# reverb3.net
KiCad netlist of a schematic drawn in EAGLE
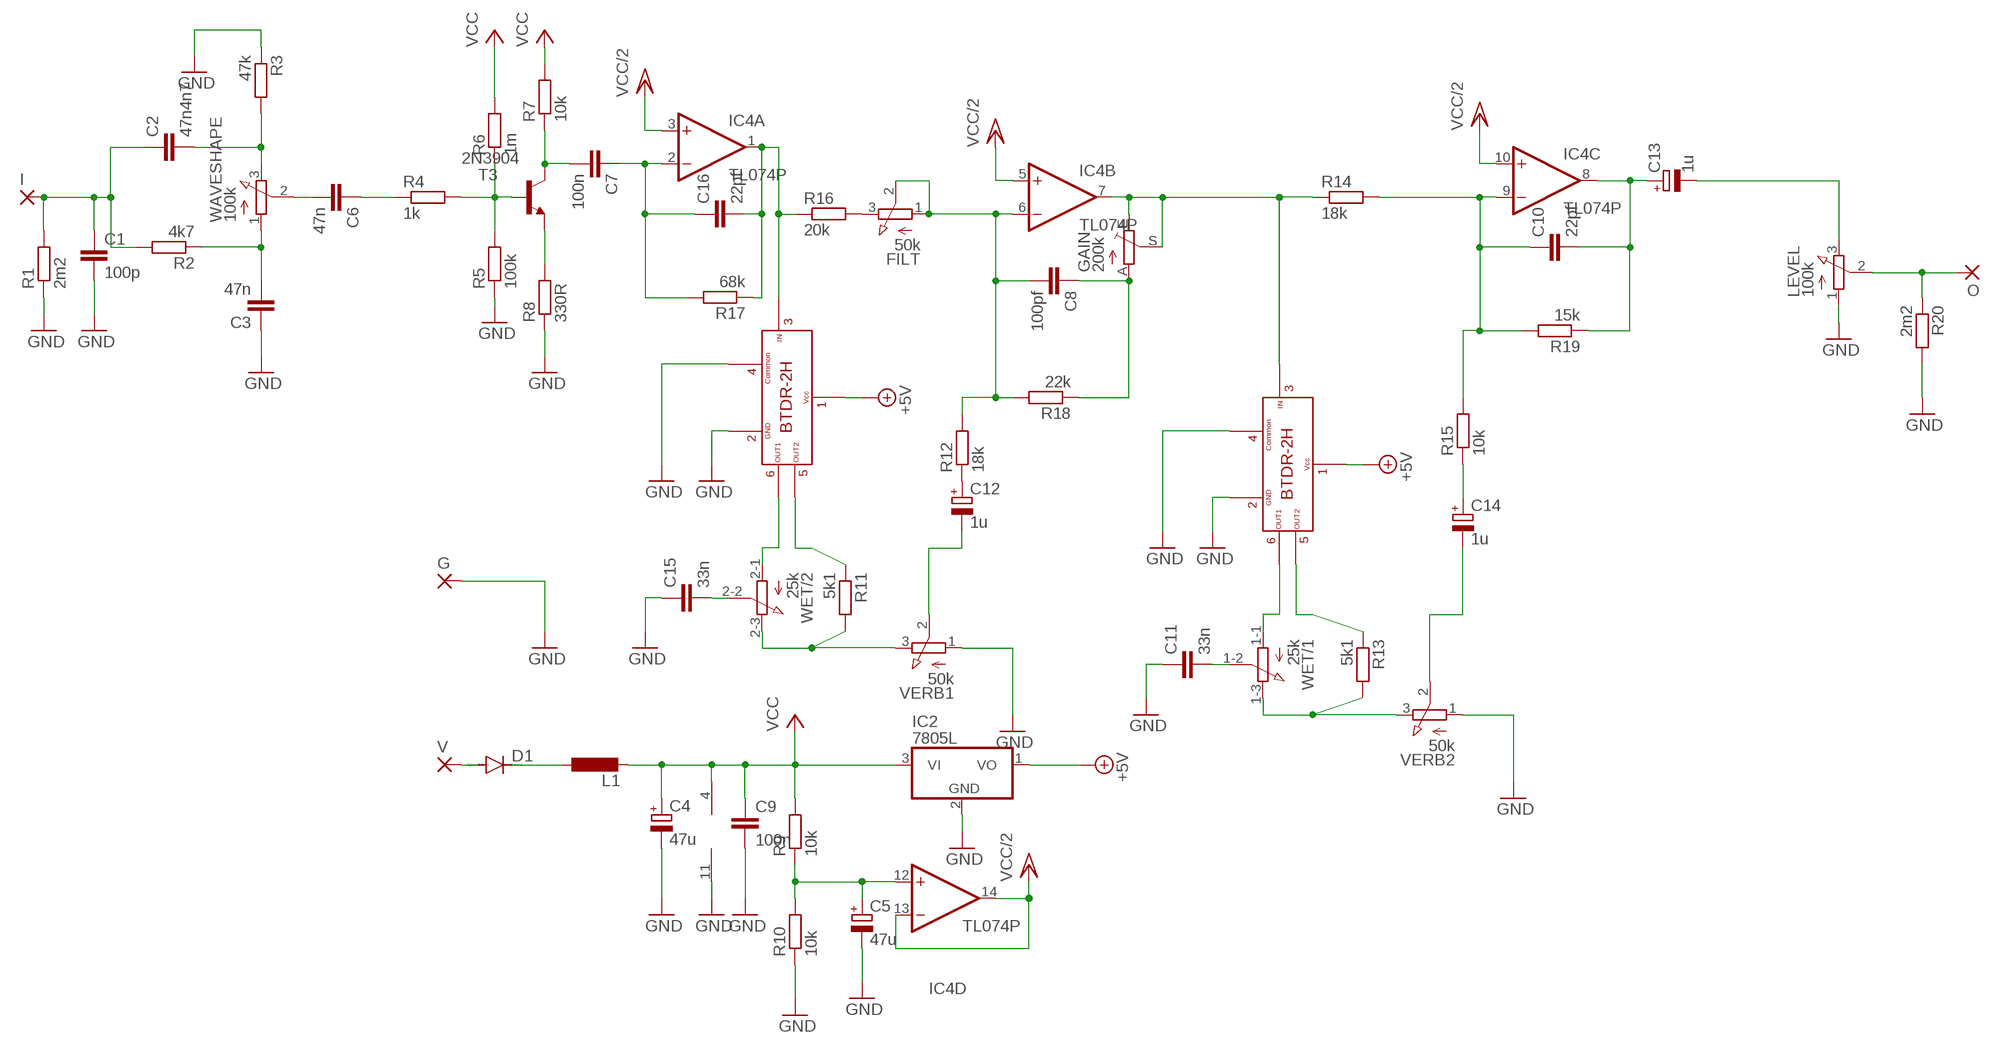
[diagram p0: schematic, sheet 1]

(export (version "E")
  (design (tool "Eeschema 10.0.6"))
  (components
    (comp (ref "BELTON1")
      (value "BTDR-2H")
      (footprint "eagle-import:BTDR2")
      (libsource (lib "eagle-import") (part "BTDR-2H"))
    )
    (comp (ref "C1")
      (value "100p")
      (footprint "eagle-import:S5MMHEXCAP")
      (libsource (lib "eagle-import") (part "C5/2.5"))
    )
    (comp (ref "C2")
      (value "47n4n7")
      (footprint "eagle-import:S5MMHEXCAP")
      (libsource (lib "eagle-import") (part "C5/2.5"))
    )
    (comp (ref "C3")
      (value "47n")
      (footprint "eagle-import:S5MMHEXCAP")
      (libsource (lib "eagle-import") (part "C5/2.5"))
    )
    (comp (ref "C4")
      (value "47u")
      (footprint "eagle-import:E2-4")
      (libsource (lib "eagle-import") (part "CPOL-EUE2-4"))
    )
    (comp (ref "C5")
      (value "47u")
      (footprint "eagle-import:E2-4")
      (libsource (lib "eagle-import") (part "CPOL-EUE2-4"))
    )
    (comp (ref "C6")
      (value "47n")
      (footprint "eagle-import:S5MMHEXCAP")
      (libsource (lib "eagle-import") (part "C5/2.5"))
    )
    (comp (ref "C7")
      (value "100n")
      (footprint "eagle-import:S5MMHEXCAP")
      (libsource (lib "eagle-import") (part "C5/2.5"))
    )
    (comp (ref "C8")
      (value "100pf")
      (footprint "eagle-import:S5MMHEXCAP")
      (libsource (lib "eagle-import") (part "C5/2.5"))
    )
    (comp (ref "C9")
      (value "100n")
      (footprint "eagle-import:S5MMHEXCAP")
      (libsource (lib "eagle-import") (part "C5/2.5"))
    )
    (comp (ref "C10")
      (value "22pf")
      (footprint "eagle-import:S5MMHEXCAP")
      (libsource (lib "eagle-import") (part "C5/2.5"))
    )
    (comp (ref "C11")
      (value "33n")
      (footprint "eagle-import:S5MMHEXCAP")
      (libsource (lib "eagle-import") (part "C5/2.5"))
    )
    (comp (ref "C12")
      (value "1u")
      (footprint "eagle-import:E2-4")
      (libsource (lib "eagle-import") (part "CPOL-EUE2-4"))
    )
    (comp (ref "C13")
      (value "1u")
      (footprint "eagle-import:E2-4")
      (libsource (lib "eagle-import") (part "CPOL-EUE2-4"))
    )
    (comp (ref "C14")
      (value "1u")
      (footprint "eagle-import:E2-4")
      (libsource (lib "eagle-import") (part "CPOL-EUE2-4"))
    )
    (comp (ref "C15")
      (value "33n")
      (footprint "eagle-import:S5MMHEXCAP")
      (libsource (lib "eagle-import") (part "C5/2.5"))
    )
    (comp (ref "C16")
      (value "22pf")
      (footprint "eagle-import:S5MMHEXCAP")
      (libsource (lib "eagle-import") (part "C5/2.5"))
    )
    (comp (ref "D1")
      (value "1N4148DO35-7")
      (footprint "eagle-import:DO35-7")
      (libsource (lib "eagle-import") (part "1N4148DO35-7"))
    )
    (comp (ref "FILT")
      (value "50k")
      (footprint "eagle-import:3RP_1610N")
      (libsource (lib "eagle-import") (part "HEXPOT1"))
    )
    (comp (ref "G")
      (value "WIREPAD1,6/0,9")
      (footprint "eagle-import:1,6_0,9")
      (libsource (lib "eagle-import") (part "WIREPAD1,6/0,9"))
    )
    (comp (ref "GAIN")
      (value "200k")
      (footprint "eagle-import:CT6")
      (libsource (lib "eagle-import") (part "TRIM_EU-CT6"))
    )
    (comp (ref "I")
      (value "WIREPAD1,6/0,9")
      (footprint "eagle-import:1,6_0,9")
      (libsource (lib "eagle-import") (part "WIREPAD1,6/0,9"))
    )
    (comp (ref "IC2")
      (value "7805L")
      (footprint "eagle-import:TO92")
      (libsource (lib "eagle-import") (part "78L05"))
    )
    (comp (ref "IC4")
      (value "TL074P")
      (footprint "eagle-import:DIL14")
      (libsource (lib "eagle-import") (part "TL074P"))
    )
    (comp (ref "L1")
      (value "L-EU0204/7")
      (footprint "eagle-import:0204_7")
      (libsource (lib "eagle-import") (part "L-EU0204/7"))
    )
    (comp (ref "LEVEL")
      (value "100k")
      (footprint "eagle-import:3RP_1610N")
      (libsource (lib "eagle-import") (part "HEXPOT1"))
    )
    (comp (ref "O")
      (value "WIREPAD1,6/0,9")
      (footprint "eagle-import:1,6_0,9")
      (libsource (lib "eagle-import") (part "WIREPAD1,6/0,9"))
    )
    (comp (ref "R1")
      (value "2m2")
      (footprint "eagle-import:0207_7")
      (libsource (lib "eagle-import") (part "R-EU_0207/7"))
    )
    (comp (ref "R2")
      (value "4k7")
      (footprint "eagle-import:0207_7")
      (libsource (lib "eagle-import") (part "R-EU_0207/7"))
    )
    (comp (ref "R3")
      (value "47k")
      (footprint "eagle-import:0207_7")
      (libsource (lib "eagle-import") (part "R-EU_0207/7"))
    )
    (comp (ref "R4")
      (value "1k")
      (footprint "eagle-import:0207_7")
      (libsource (lib "eagle-import") (part "R-EU_0207/7"))
    )
    (comp (ref "R5")
      (value "100k")
      (footprint "eagle-import:0207_7")
      (libsource (lib "eagle-import") (part "R-EU_0207/7"))
    )
    (comp (ref "R6")
      (value "1m")
      (footprint "eagle-import:0207_7")
      (libsource (lib "eagle-import") (part "R-EU_0207/7"))
    )
    (comp (ref "R7")
      (value "10k")
      (footprint "eagle-import:0207_7")
      (libsource (lib "eagle-import") (part "R-EU_0207/7"))
    )
    (comp (ref "R8")
      (value "330R")
      (footprint "eagle-import:0207_7")
      (libsource (lib "eagle-import") (part "R-EU_0207/7"))
    )
    (comp (ref "R9")
      (value "10k")
      (footprint "eagle-import:0207_7")
      (libsource (lib "eagle-import") (part "R-EU_0207/7"))
    )
    (comp (ref "R10")
      (value "10k")
      (footprint "eagle-import:0207_7")
      (libsource (lib "eagle-import") (part "R-EU_0207/7"))
    )
    (comp (ref "R11")
      (value "5k1")
      (footprint "eagle-import:0207_7")
      (libsource (lib "eagle-import") (part "R-EU_0207/7"))
    )
    (comp (ref "R12")
      (value "18k")
      (footprint "eagle-import:0207_7")
      (libsource (lib "eagle-import") (part "R-EU_0207/7"))
    )
    (comp (ref "R13")
      (value "5k1")
      (footprint "eagle-import:0207_7")
      (libsource (lib "eagle-import") (part "R-EU_0207/7"))
    )
    (comp (ref "R14")
      (value "18k")
      (footprint "eagle-import:0207_7")
      (libsource (lib "eagle-import") (part "R-EU_0207/7"))
    )
    (comp (ref "R15")
      (value "10k")
      (footprint "eagle-import:0207_7")
      (libsource (lib "eagle-import") (part "R-EU_0207/7"))
    )
    (comp (ref "R16")
      (value "20k")
      (footprint "eagle-import:0207_7")
      (libsource (lib "eagle-import") (part "R-EU_0207/7"))
    )
    (comp (ref "R17")
      (value "68k")
      (footprint "eagle-import:0207_7")
      (libsource (lib "eagle-import") (part "R-EU_0207/7"))
    )
    (comp (ref "R18")
      (value "22k")
      (footprint "eagle-import:0207_7")
      (libsource (lib "eagle-import") (part "R-EU_0207/7"))
    )
    (comp (ref "R19")
      (value "15k")
      (footprint "eagle-import:0207_7")
      (libsource (lib "eagle-import") (part "R-EU_0207/7"))
    )
    (comp (ref "R20")
      (value "2m2")
      (footprint "eagle-import:0207_7")
      (libsource (lib "eagle-import") (part "R-EU_0207/7"))
    )
    (comp (ref "T3")
      (value "2N3904")
      (footprint "eagle-import:TO92")
      (libsource (lib "eagle-import") (part "2N3904"))
    )
    (comp (ref "U$2")
      (value "BTDR-2H")
      (footprint "eagle-import:BTDR2")
      (libsource (lib "eagle-import") (part "BTDR-2H"))
    )
    (comp (ref "V")
      (value "WIREPAD1,6/0,9")
      (footprint "eagle-import:1,6_0,9")
      (libsource (lib "eagle-import") (part "WIREPAD1,6/0,9"))
    )
    (comp (ref "VERB1")
      (value "50k")
      (footprint "eagle-import:3RP_1610N")
      (libsource (lib "eagle-import") (part "HEXPOT1"))
    )
    (comp (ref "VERB2")
      (value "50k")
      (footprint "eagle-import:3RP_1610N")
      (libsource (lib "eagle-import") (part "HEXPOT1"))
    )
    (comp (ref "WAVESHAPE")
      (value "100k")
      (footprint "eagle-import:3RP_1610N")
      (libsource (lib "eagle-import") (part "HEXPOT1"))
    )
    (comp (ref "WET")
      (value "25k")
      (footprint "eagle-import:3RP_1610G")
      (libsource (lib "eagle-import") (part "3RP/1610G"))
    )
  )
  (nets
    (net (code "1") (name "+5V") (class "Default")
      (node (ref "BELTON1") (pin "P$1") (pinfunction "P$1_P$1") (pintype "bidirectional"))
      (node (ref "IC2") (pin "1") (pinfunction "VO_1") (pintype "passive"))
      (node (ref "U$2") (pin "P$1") (pinfunction "P$1_P$1") (pintype "bidirectional"))
    )
    (net (code "2") (name "GND") (class "Default")
      (node (ref "BELTON1") (pin "P$2") (pinfunction "P$2_P$2") (pintype "bidirectional"))
      (node (ref "BELTON1") (pin "P$4") (pinfunction "P$4_P$4") (pintype "bidirectional"))
      (node (ref "C1") (pin "2") (pinfunction "2_2") (pintype "passive"))
      (node (ref "C11") (pin "1") (pinfunction "1_1") (pintype "passive"))
      (node (ref "C15") (pin "1") (pinfunction "1_1") (pintype "passive"))
      (node (ref "C3") (pin "1") (pinfunction "1_1") (pintype "passive"))
      (node (ref "C4") (pin "-") (pinfunction "-_-") (pintype "passive"))
      (node (ref "C5") (pin "-") (pinfunction "-_-") (pintype "passive"))
      (node (ref "C9") (pin "2") (pinfunction "2_2") (pintype "passive"))
      (node (ref "G") (pin "1") (pinfunction "P_1") (pintype "passive"))
      (node (ref "IC2") (pin "2") (pinfunction "GND_2") (pintype "passive"))
      (node (ref "IC4") (pin "11") (pinfunction "V-_11") (pintype "power_in"))
      (node (ref "LEVEL") (pin "1") (pinfunction "A_1") (pintype "passive"))
      (node (ref "R1") (pin "1") (pinfunction "1_1") (pintype "passive"))
      (node (ref "R10") (pin "1") (pinfunction "1_1") (pintype "passive"))
      (node (ref "R20") (pin "2") (pinfunction "2_2") (pintype "passive"))
      (node (ref "R3") (pin "1") (pinfunction "1_1") (pintype "passive"))
      (node (ref "R5") (pin "1") (pinfunction "1_1") (pintype "passive"))
      (node (ref "R8") (pin "1") (pinfunction "1_1") (pintype "passive"))
      (node (ref "U$2") (pin "P$2") (pinfunction "P$2_P$2") (pintype "bidirectional"))
      (node (ref "U$2") (pin "P$4") (pinfunction "P$4_P$4") (pintype "bidirectional"))
      (node (ref "VERB1") (pin "1") (pinfunction "A_1") (pintype "passive"))
      (node (ref "VERB2") (pin "1") (pinfunction "A_1") (pintype "passive"))
    )
    (net (code "3") (name "Net-(BELTON1-PadP$5)") (class "Default")
      (node (ref "BELTON1") (pin "P$5") (pinfunction "P$5_P$5") (pintype "bidirectional"))
      (node (ref "R13") (pin "1") (pinfunction "1_1") (pintype "passive"))
    )
    (net (code "4") (name "Net-(C6-Pad1)") (class "Default")
      (node (ref "C6") (pin "1") (pinfunction "1_1") (pintype "passive"))
      (node (ref "R4") (pin "1") (pinfunction "1_1") (pintype "passive"))
    )
    (net (code "5") (name "Net-(C8-Pad1)") (class "Default")
      (node (ref "C8") (pin "1") (pinfunction "1_1") (pintype "passive"))
      (node (ref "GAIN") (pin "A") (pinfunction "A_A") (pintype "passive"))
      (node (ref "R18") (pin "1") (pinfunction "1_1") (pintype "passive"))
    )
    (net (code "6") (name "Net-(C12-Pad+)") (class "Default")
      (node (ref "C12") (pin "+") (pinfunction "+_+") (pintype "passive"))
      (node (ref "R12") (pin "1") (pinfunction "1_1") (pintype "passive"))
    )
    (net (code "7") (name "Net-(C14-Pad+)") (class "Default")
      (node (ref "C14") (pin "+") (pinfunction "+_+") (pintype "passive"))
      (node (ref "R15") (pin "1") (pinfunction "1_1") (pintype "passive"))
    )
    (net (code "8") (name "Net-(D1-PadC)") (class "Default")
      (node (ref "D1") (pin "C") (pinfunction "C_C") (pintype "passive"))
      (node (ref "L1") (pin "1") (pinfunction "1_1") (pintype "passive"))
    )
    (net (code "9") (name "Net-(FILT-A)") (class "Default")
      (node (ref "C8") (pin "2") (pinfunction "2_2") (pintype "passive"))
      (node (ref "FILT") (pin "1") (pinfunction "A_1") (pintype "passive"))
      (node (ref "FILT") (pin "2") (pinfunction "S_2") (pintype "passive"))
      (node (ref "IC4") (pin "6") (pinfunction "-IN_6") (pintype "input"))
      (node (ref "R12") (pin "2") (pinfunction "2_2") (pintype "passive"))
      (node (ref "R18") (pin "2") (pinfunction "2_2") (pintype "passive"))
    )
    (net (code "10") (name "Net-(FILT-E)") (class "Default")
      (node (ref "FILT") (pin "3") (pinfunction "E_3") (pintype "passive"))
      (node (ref "R16") (pin "2") (pinfunction "2_2") (pintype "passive"))
    )
    (net (code "11") (name "Net-(I-P)") (class "Default")
      (node (ref "C1") (pin "1") (pinfunction "1_1") (pintype "passive"))
      (node (ref "C2") (pin "1") (pinfunction "1_1") (pintype "passive"))
      (node (ref "I") (pin "1") (pinfunction "P_1") (pintype "passive"))
      (node (ref "R1") (pin "2") (pinfunction "2_2") (pintype "passive"))
      (node (ref "R2") (pin "2") (pinfunction "2_2") (pintype "passive"))
    )
    (net (code "12") (name "Net-(IC4A--IN)") (class "Default")
      (node (ref "C16") (pin "1") (pinfunction "1_1") (pintype "passive"))
      (node (ref "C7") (pin "1") (pinfunction "1_1") (pintype "passive"))
      (node (ref "IC4") (pin "2") (pinfunction "-IN_2") (pintype "input"))
      (node (ref "R17") (pin "2") (pinfunction "2_2") (pintype "passive"))
    )
    (net (code "13") (name "Net-(IC4A-OUT)") (class "Default")
      (node (ref "C16") (pin "2") (pinfunction "2_2") (pintype "passive"))
      (node (ref "IC4") (pin "1") (pinfunction "OUT_1") (pintype "output"))
      (node (ref "R16") (pin "1") (pinfunction "1_1") (pintype "passive"))
      (node (ref "R17") (pin "1") (pinfunction "1_1") (pintype "passive"))
      (node (ref "U$2") (pin "P$3") (pinfunction "P$3_P$3") (pintype "bidirectional"))
    )
    (net (code "14") (name "Net-(IC4B-OUT)") (class "Default")
      (node (ref "BELTON1") (pin "P$3") (pinfunction "P$3_P$3") (pintype "bidirectional"))
      (node (ref "GAIN") (pin "E") (pinfunction "E_E") (pintype "passive"))
      (node (ref "GAIN") (pin "S") (pinfunction "S_S") (pintype "passive"))
      (node (ref "IC4") (pin "7") (pinfunction "OUT_7") (pintype "output"))
      (node (ref "R14") (pin "1") (pinfunction "1_1") (pintype "passive"))
    )
    (net (code "15") (name "Net-(IC4C--IN)") (class "Default")
      (node (ref "C10") (pin "1") (pinfunction "1_1") (pintype "passive"))
      (node (ref "IC4") (pin "9") (pinfunction "-IN_9") (pintype "input"))
      (node (ref "R14") (pin "2") (pinfunction "2_2") (pintype "passive"))
      (node (ref "R15") (pin "2") (pinfunction "2_2") (pintype "passive"))
      (node (ref "R19") (pin "2") (pinfunction "2_2") (pintype "passive"))
    )
    (net (code "16") (name "Net-(IC4C-OUT)") (class "Default")
      (node (ref "C10") (pin "2") (pinfunction "2_2") (pintype "passive"))
      (node (ref "C13") (pin "+") (pinfunction "+_+") (pintype "passive"))
      (node (ref "IC4") (pin "8") (pinfunction "OUT_8") (pintype "output"))
      (node (ref "R19") (pin "1") (pinfunction "1_1") (pintype "passive"))
    )
    (net (code "17") (name "Net-(IC4D-+IN)") (class "Default")
      (node (ref "C5") (pin "+") (pinfunction "+_+") (pintype "passive"))
      (node (ref "IC4") (pin "12") (pinfunction "+IN_12") (pintype "input"))
      (node (ref "R10") (pin "2") (pinfunction "2_2") (pintype "passive"))
      (node (ref "R9") (pin "1") (pinfunction "1_1") (pintype "passive"))
    )
    (net (code "18") (name "Net-(LEVEL-E)") (class "Default")
      (node (ref "C13") (pin "-") (pinfunction "-_-") (pintype "passive"))
      (node (ref "LEVEL") (pin "3") (pinfunction "E_3") (pintype "passive"))
    )
    (net (code "19") (name "Net-(LEVEL-S)") (class "Default")
      (node (ref "LEVEL") (pin "2") (pinfunction "S_2") (pintype "passive"))
      (node (ref "O") (pin "1") (pinfunction "P_1") (pintype "passive"))
      (node (ref "R20") (pin "1") (pinfunction "1_1") (pintype "passive"))
    )
    (net (code "20") (name "Net-(R11-Pad1)") (class "Default")
      (node (ref "R11") (pin "1") (pinfunction "1_1") (pintype "passive"))
      (node (ref "U$2") (pin "P$5") (pinfunction "P$5_P$5") (pintype "bidirectional"))
    )
    (net (code "21") (name "Net-(T3-B)") (class "Default")
      (node (ref "R4") (pin "2") (pinfunction "2_2") (pintype "passive"))
      (node (ref "R5") (pin "2") (pinfunction "2_2") (pintype "passive"))
      (node (ref "R6") (pin "1") (pinfunction "1_1") (pintype "passive"))
      (node (ref "T3") (pin "2") (pinfunction "B_2") (pintype "passive"))
    )
    (net (code "22") (name "Net-(T3-C)") (class "Default")
      (node (ref "C7") (pin "2") (pinfunction "2_2") (pintype "passive"))
      (node (ref "R7") (pin "1") (pinfunction "1_1") (pintype "passive"))
      (node (ref "T3") (pin "1") (pinfunction "C_1") (pintype "passive"))
    )
    (net (code "23") (name "Net-(T3-E)") (class "Default")
      (node (ref "R8") (pin "2") (pinfunction "2_2") (pintype "passive"))
      (node (ref "T3") (pin "3") (pinfunction "E_3") (pintype "passive"))
    )
    (net (code "24") (name "Net-(V-P)") (class "Default")
      (node (ref "D1") (pin "A") (pinfunction "A_A") (pintype "passive"))
      (node (ref "V") (pin "1") (pinfunction "P_1") (pintype "passive"))
    )
    (net (code "25") (name "Net-(VERB1-E)") (class "Default")
      (node (ref "R11") (pin "2") (pinfunction "2_2") (pintype "passive"))
      (node (ref "VERB1") (pin "3") (pinfunction "E_3") (pintype "passive"))
      (node (ref "WET") (pin "2-3") (pinfunction "E_2-3") (pintype "passive"))
    )
    (net (code "26") (name "Net-(VERB1-S)") (class "Default")
      (node (ref "C12") (pin "-") (pinfunction "-_-") (pintype "passive"))
      (node (ref "VERB1") (pin "2") (pinfunction "S_2") (pintype "passive"))
    )
    (net (code "27") (name "Net-(VERB2-E)") (class "Default")
      (node (ref "R13") (pin "2") (pinfunction "2_2") (pintype "passive"))
      (node (ref "VERB2") (pin "3") (pinfunction "E_3") (pintype "passive"))
      (node (ref "WET") (pin "1-3") (pinfunction "E_1-3") (pintype "passive"))
    )
    (net (code "28") (name "Net-(VERB2-S)") (class "Default")
      (node (ref "C14") (pin "-") (pinfunction "-_-") (pintype "passive"))
      (node (ref "VERB2") (pin "2") (pinfunction "S_2") (pintype "passive"))
    )
    (net (code "29") (name "Net-(WAVESHAPE-A)") (class "Default")
      (node (ref "C3") (pin "2") (pinfunction "2_2") (pintype "passive"))
      (node (ref "R2") (pin "1") (pinfunction "1_1") (pintype "passive"))
      (node (ref "WAVESHAPE") (pin "1") (pinfunction "A_1") (pintype "passive"))
    )
    (net (code "30") (name "Net-(WAVESHAPE-E)") (class "Default")
      (node (ref "C2") (pin "2") (pinfunction "2_2") (pintype "passive"))
      (node (ref "R3") (pin "2") (pinfunction "2_2") (pintype "passive"))
      (node (ref "WAVESHAPE") (pin "3") (pinfunction "E_3") (pintype "passive"))
    )
    (net (code "31") (name "Net-(WAVESHAPE-S)") (class "Default")
      (node (ref "C6") (pin "2") (pinfunction "2_2") (pintype "passive"))
      (node (ref "WAVESHAPE") (pin "2") (pinfunction "S_2") (pintype "passive"))
    )
    (net (code "32") (name "Net-(WETA-A)") (class "Default")
      (node (ref "BELTON1") (pin "P$6") (pinfunction "P$6_P$6") (pintype "bidirectional"))
      (node (ref "WET") (pin "1-1") (pinfunction "A_1-1") (pintype "passive"))
    )
    (net (code "33") (name "Net-(WETA-S)") (class "Default")
      (node (ref "C11") (pin "2") (pinfunction "2_2") (pintype "passive"))
      (node (ref "WET") (pin "1-2") (pinfunction "S_1-2") (pintype "passive"))
    )
    (net (code "34") (name "Net-(WETB-A)") (class "Default")
      (node (ref "U$2") (pin "P$6") (pinfunction "P$6_P$6") (pintype "bidirectional"))
      (node (ref "WET") (pin "2-1") (pinfunction "A_2-1") (pintype "passive"))
    )
    (net (code "35") (name "Net-(WETB-S)") (class "Default")
      (node (ref "C15") (pin "2") (pinfunction "2_2") (pintype "passive"))
      (node (ref "WET") (pin "2-2") (pinfunction "S_2-2") (pintype "passive"))
    )
    (net (code "36") (name "VCC") (class "Default")
      (node (ref "C4") (pin "+") (pinfunction "+_+") (pintype "passive"))
      (node (ref "C9") (pin "1") (pinfunction "1_1") (pintype "passive"))
      (node (ref "IC2") (pin "3") (pinfunction "VI_3") (pintype "input"))
      (node (ref "IC4") (pin "4") (pinfunction "V+_4") (pintype "power_in"))
      (node (ref "L1") (pin "2") (pinfunction "2_2") (pintype "passive"))
      (node (ref "R6") (pin "2") (pinfunction "2_2") (pintype "passive"))
      (node (ref "R7") (pin "2") (pinfunction "2_2") (pintype "passive"))
      (node (ref "R9") (pin "2") (pinfunction "2_2") (pintype "passive"))
    )
    (net (code "37") (name "VCC{slash}2") (class "Default")
      (node (ref "IC4") (pin "10") (pinfunction "+IN_10") (pintype "input"))
      (node (ref "IC4") (pin "13") (pinfunction "-IN_13") (pintype "input"))
      (node (ref "IC4") (pin "14") (pinfunction "OUT_14") (pintype "output"))
      (node (ref "IC4") (pin "3") (pinfunction "+IN_3") (pintype "input"))
      (node (ref "IC4") (pin "5") (pinfunction "+IN_5") (pintype "input"))
    )
  )
)
